# 20_Conector.net
KiCad netlist of a schematic drawn in Altium Designer
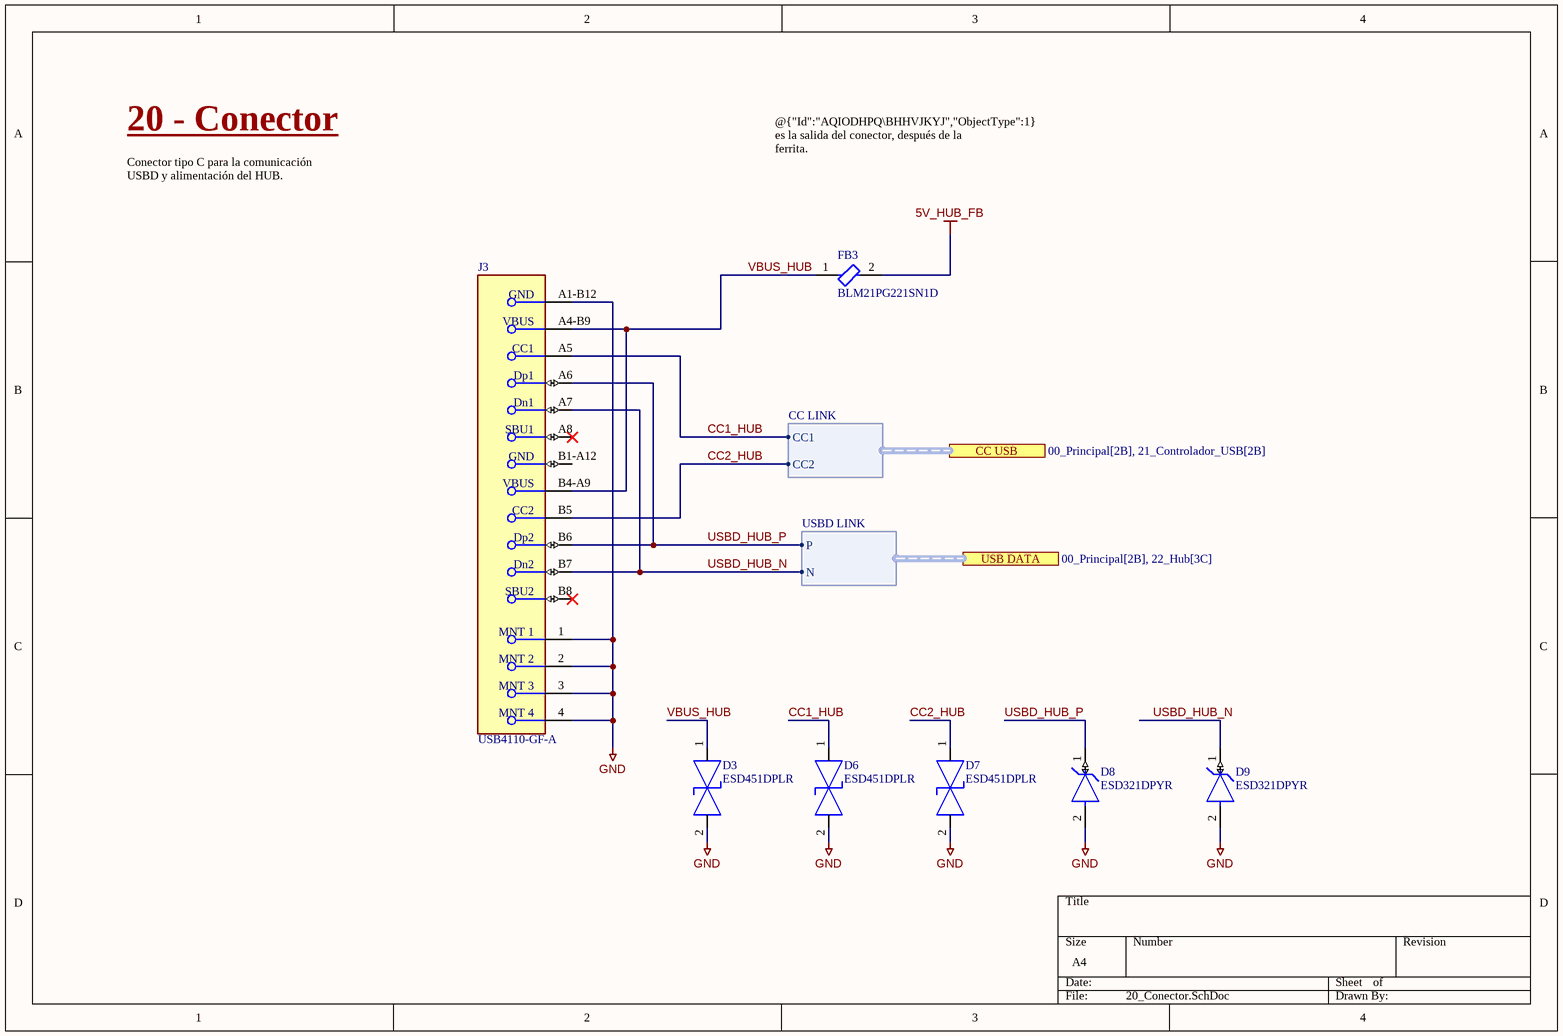
[diagram p0: 20_Conector.SchDoc]

(export (version "E")
  (design (tool "Eeschema 10.0.6"))
  (components
    (comp (ref "D3")
      (value "ESD451DPLR")
      (footprint "FP-DPL0002A_MFG")
      (description "0.5-pF, 5.5-V, 30-KV bidirectional ESD protection device in 0201 package 2-X2SON -40 to 125")
      (libsource (lib "Altium Content Vault") (part "ef80418522d6051962dd4b26d32e366"))
    )
    (comp (ref "D6")
      (value "ESD451DPLR")
      (footprint "FP-DPL0002A_MFG")
      (description "0.5-pF, 5.5-V, 30-KV bidirectional ESD protection device in 0201 package 2-X2SON -40 to 125")
      (libsource (lib "Altium Content Vault") (part "ef80418522d6051962dd4b26d32e366"))
    )
    (comp (ref "D7")
      (value "ESD451DPLR")
      (footprint "FP-DPL0002A_MFG")
      (description "0.5-pF, 5.5-V, 30-KV bidirectional ESD protection device in 0201 package 2-X2SON -40 to 125")
      (libsource (lib "Altium Content Vault") (part "ef80418522d6051962dd4b26d32e366"))
    )
    (comp (ref "D8")
      (value "ESD321DPYR")
      (footprint "FP-DPY0002A-MFG")
      (description "HDMI2.0 ESD PROTECTION")
      (fields
        (field (name "OCTOPART") "https://octopart.com/esd321dpyr-texas+instruments-94354200")
        (field (name "MANUFACTURER") "Texas Instruments")
      )
      (libsource (lib "Altium Content Vault") (part "66ee42db3b8e3650e8893baa18e0b41"))
    )
    (comp (ref "D9")
      (value "ESD321DPYR")
      (footprint "FP-DPY0002A-MFG")
      (description "HDMI2.0 ESD PROTECTION")
      (fields
        (field (name "OCTOPART") "https://octopart.com/esd321dpyr-texas+instruments-94354200")
        (field (name "MANUFACTURER") "Texas Instruments")
      )
      (libsource (lib "Altium Content Vault") (part "66ee42db3b8e3650e8893baa18e0b41"))
    )
    (comp (ref "FB3")
      (value "BLM21PG221SN1D")
      (footprint "FP-BLM21-0_2-t0_85-e0_5-IPC_B")
      (description "Chip Ferrite Bead, 0805, 220Ω @ 100MHz, 0.045Ω, 25%, 2A")
      (fields (field (name "TOLERANCE") "25%"))
      (libsource (lib "Altium Content Vault") (part "5f30dd21d616792df468990f7003faa"))
    )
    (comp (ref "J3")
      (value "USB4110-GF-A")
      (footprint "FP-USB4110-GF-A-MFG")
      (description "CONN USB 2.0 TYPE-C R/A SMT")
      (fields
        (field (name "OCTOPART") "https://octopart.com/usb4110-gf-a-gct-103941985")
        (field (name "MANUFACTURER") "GCT")
      )
      (libsource (lib "Altium Content Vault") (part "e23f2b38bb3c3f98e683ebab9ede730"))
    )
  )
  (nets
    (net (code "4") (name "/CC1_HUB") (class "Default")
      (node (ref "D6") (pin "1") (pinfunction "1_IO_1") (pintype "passive"))
      (node (ref "J3") (pin "A5") (pinfunction "CC1_A5") (pintype "passive"))
    )
    (net (code "5") (name "/CC2_HUB") (class "Default")
      (node (ref "D7") (pin "1") (pinfunction "1_IO_1") (pintype "passive"))
      (node (ref "J3") (pin "B5") (pinfunction "CC2_B5") (pintype "passive"))
    )
    (net (code "6") (name "/USBD_HUB_N") (class "Default")
      (node (ref "D9") (pin "1") (pinfunction "IO_1") (pintype "bidirectional"))
      (node (ref "J3") (pin "A7") (pinfunction "Dn1_A7") (pintype "bidirectional"))
      (node (ref "J3") (pin "B7") (pinfunction "Dn2_B7") (pintype "bidirectional"))
    )
    (net (code "7") (name "/USBD_HUB_P") (class "Default")
      (node (ref "D8") (pin "1") (pinfunction "IO_1") (pintype "bidirectional"))
      (node (ref "J3") (pin "A6") (pinfunction "Dp1_A6") (pintype "bidirectional"))
      (node (ref "J3") (pin "B6") (pinfunction "Dp2_B6") (pintype "bidirectional"))
    )
    (net (code "8") (name "/VBUS_HUB") (class "Default")
      (node (ref "D3") (pin "1") (pinfunction "1_IO_1") (pintype "passive"))
      (node (ref "FB3") (pin "1") (pinfunction "1_1") (pintype "passive"))
      (node (ref "J3") (pin "A4-B9") (pinfunction "VBUS_A4-B9") (pintype "power_in"))
      (node (ref "J3") (pin "B4-A9") (pinfunction "VBUS_B4-A9") (pintype "power_in"))
    )
    (net (code "11") (name "5V_HUB_FB") (class "Default")
      (node (ref "FB3") (pin "2") (pinfunction "2_2") (pintype "passive"))
    )
    (net (code "12") (name "GND") (class "Default")
      (node (ref "D3") (pin "2") (pinfunction "2_IO_2") (pintype "passive"))
      (node (ref "D6") (pin "2") (pinfunction "2_IO_2") (pintype "passive"))
      (node (ref "D7") (pin "2") (pinfunction "2_IO_2") (pintype "passive"))
      (node (ref "D8") (pin "2") (pinfunction "GND_2") (pintype "power_in"))
      (node (ref "D9") (pin "2") (pinfunction "GND_2") (pintype "power_in"))
      (node (ref "J3") (pin "1") (pinfunction "MNT_1_1") (pintype "passive"))
      (node (ref "J3") (pin "2") (pinfunction "MNT_2_2") (pintype "passive"))
      (node (ref "J3") (pin "3") (pinfunction "MNT_3_3") (pintype "passive"))
      (node (ref "J3") (pin "4") (pinfunction "MNT_4_4") (pintype "passive"))
      (node (ref "J3") (pin "A1-B12") (pinfunction "GND_A1-B12") (pintype "passive"))
    )
    (net (code "13") (name "unconnected-(J3-GND-PadB1-A12)") (class "Default")
      (node (ref "J3") (pin "B1-A12") (pinfunction "GND_B1-A12") (pintype "bidirectional"))
    )
    (net (code "14") (name "unconnected-(J3-SBU1-PadA8)") (class "Default")
      (node (ref "J3") (pin "A8") (pinfunction "SBU1_A8") (pintype "bidirectional+no_connect"))
    )
    (net (code "15") (name "unconnected-(J3-SBU2-PadB8)") (class "Default")
      (node (ref "J3") (pin "B8") (pinfunction "SBU2_B8") (pintype "bidirectional+no_connect"))
    )
  )
)
